# SCH2024-02-13.net
KiCad netlist of a schematic drawn in EasyEDA
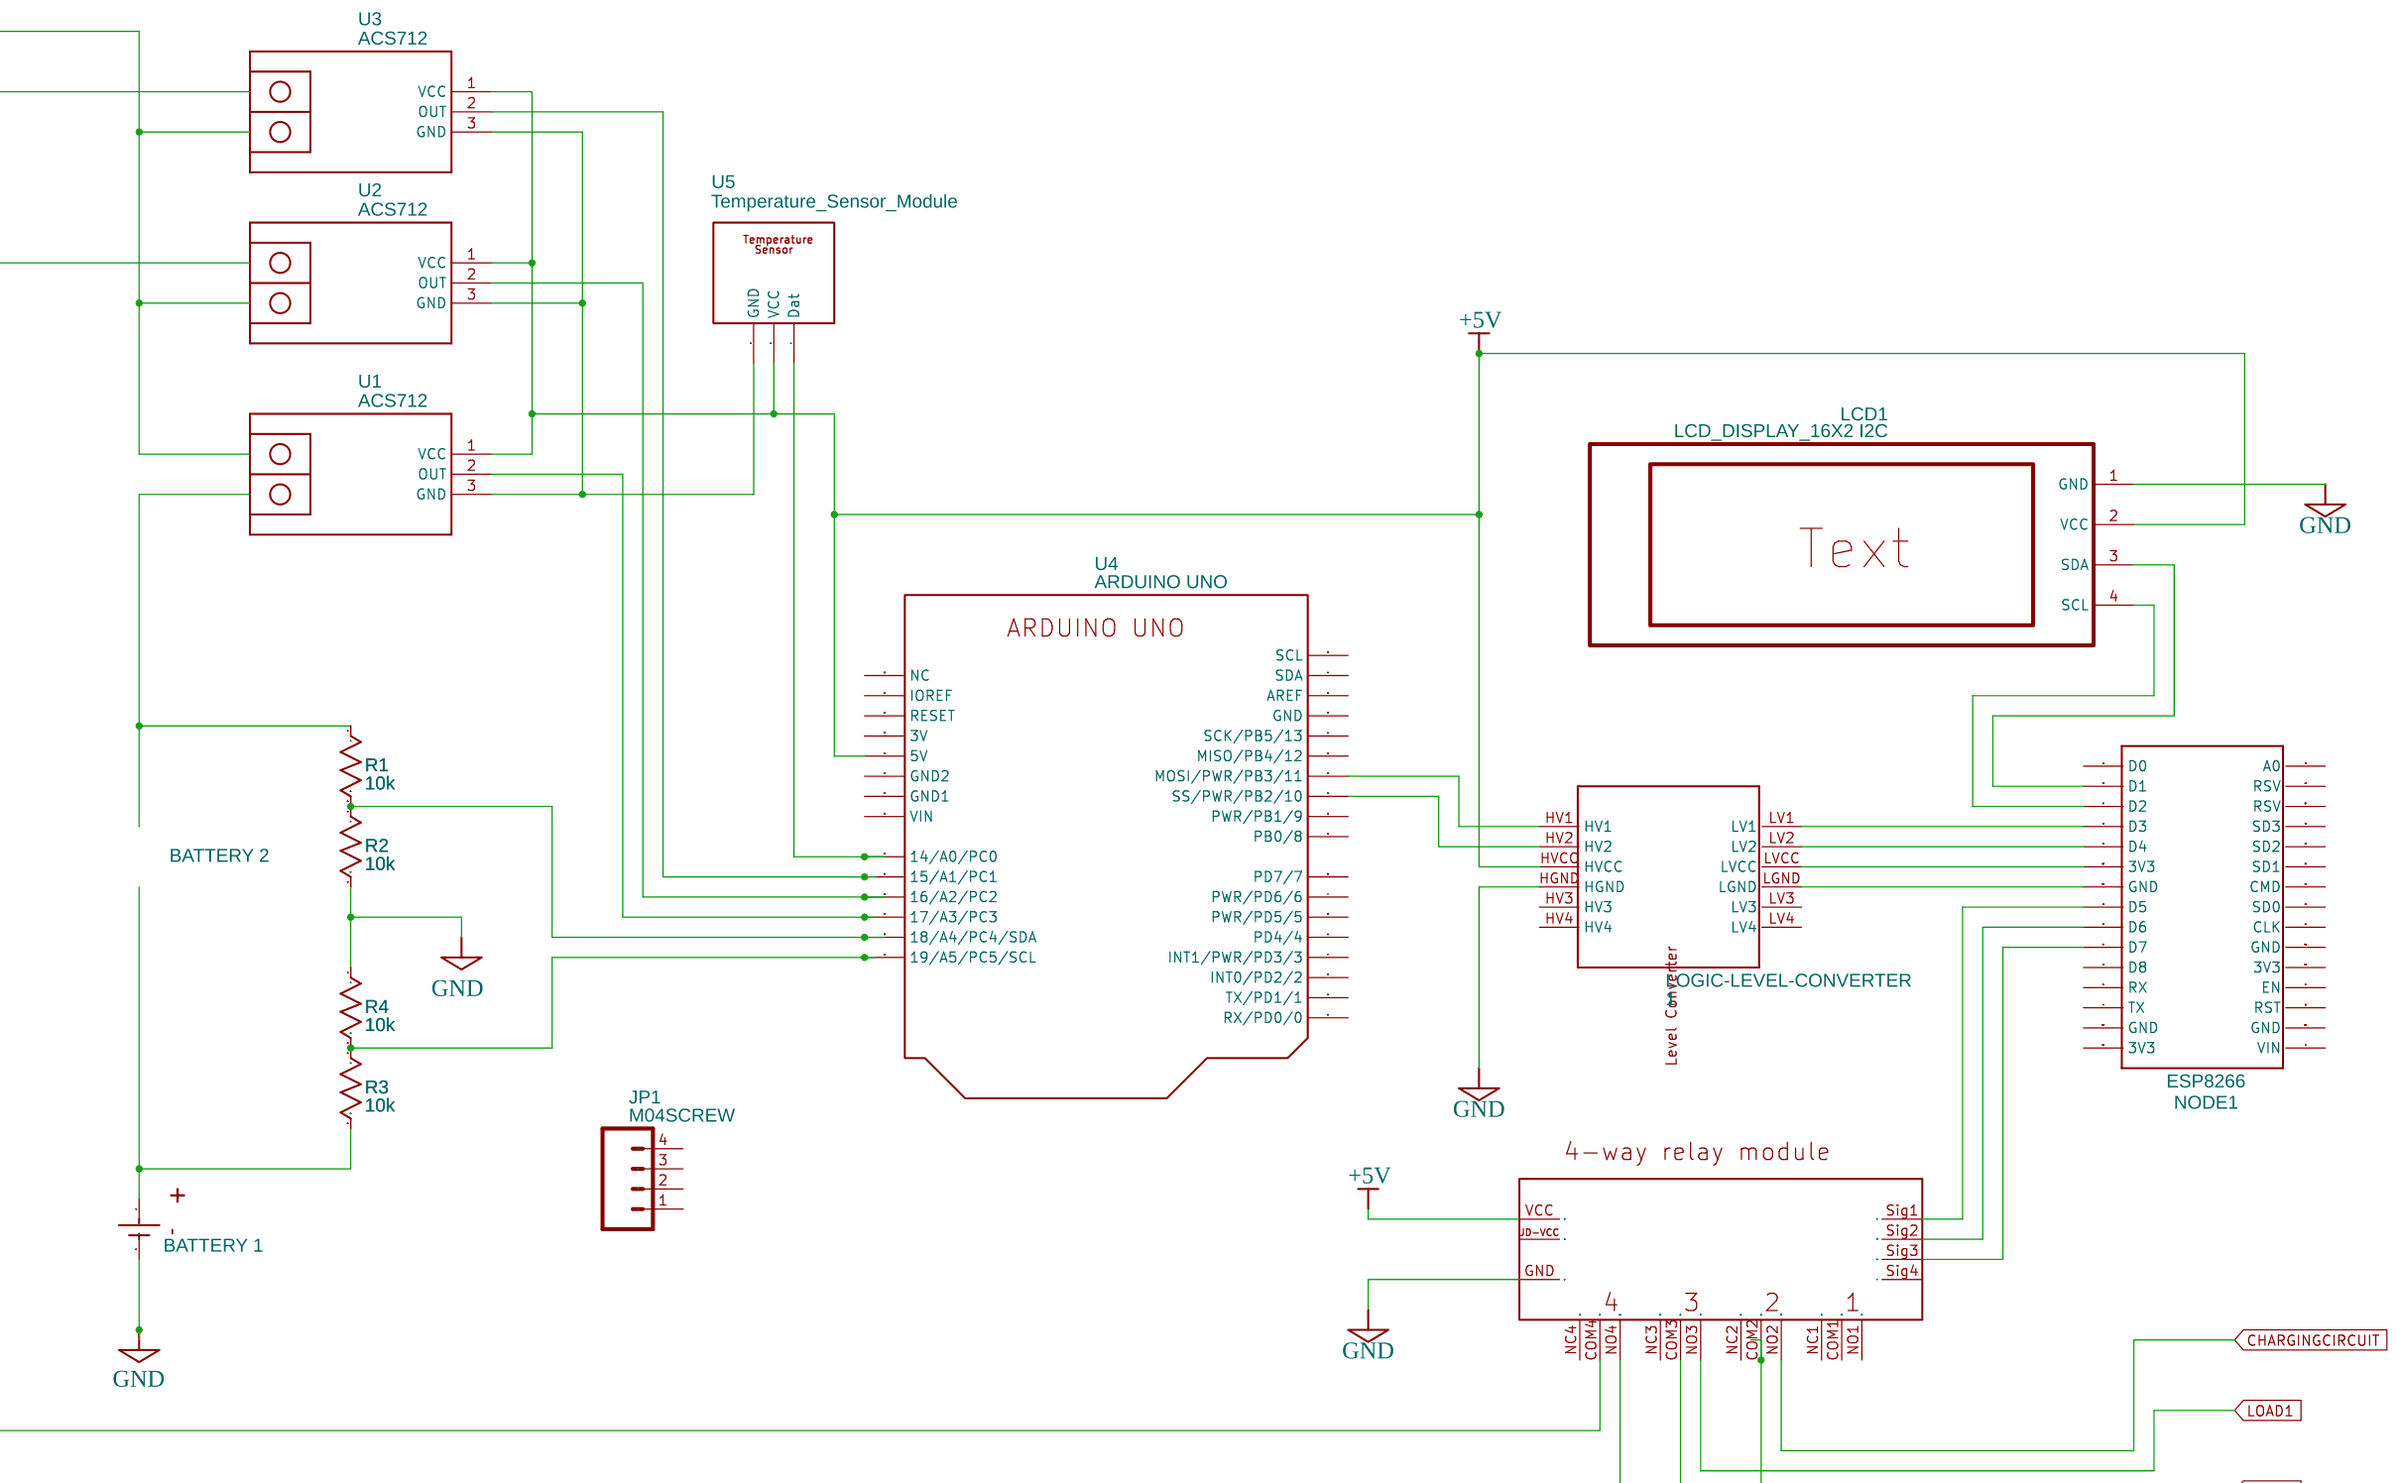
[diagram p0: schematic sheet]

(export (version "E")
  (design (tool "Eeschema 10.0.6"))
  (components
    (comp (ref "1") (value "LOGIC-LEVEL-CONVERTER") (libsource (lib "") (part "LOGIC-LEVEL-CONVERTER")))
    (comp (ref "G2") (value "BATTERY 1") (libsource (lib "") (part "BATTERY-1ELEMENT_RevE_Date15jun2010")))
    (comp (ref "JP1") (value "M04SCREW") (libsource (lib "") (part "M04SCREW")))
    (comp (ref "LCD1") (value "LCD_DISPLAY_16X2 I2C") (libsource (lib "") (part "LCD_DISPLAY_16X2 I2C")))
    (comp (ref "NODE1") (value "ESP8266") (libsource (lib "") (part "ESP8266 COPY")))
    (comp (ref "R1") (value "10k") (libsource (lib "") (part "R_0603_US")))
    (comp (ref "R2") (value "10k") (libsource (lib "") (part "R_0603_US")))
    (comp (ref "R3") (value "10k") (libsource (lib "") (part "R_0603_US")))
    (comp (ref "R4") (value "10k") (libsource (lib "") (part "R_0603_US")))
    (comp (ref "U1") (value "ACS712") (libsource (lib "") (part "CURRENT-SENSOR-ACS712")))
    (comp (ref "U2") (value "ACS712") (libsource (lib "") (part "CURRENT-SENSOR-ACS712")))
    (comp (ref "U3") (value "ACS712") (libsource (lib "") (part "CURRENT-SENSOR-ACS712")))
    (comp (ref "U4") (value "ARDUINO UNO") (libsource (lib "") (part "ARDUINO UNO")))
    (comp (ref "U5")
      (value "Temperature_Sensor_Module")
      (libsource (lib "") (part "DS18B20_Temperature_Sensor_Module"))
    )
    (comp (ref "U6") (value "4 way relay") (libsource (lib "") (part "4 way relay")))
  )
  (nets
    (net (code "1") (name "+5V") (class "Default")
      (node (ref "1") (pin "HVCC") (pinfunction "HVCC_HVCC") (pintype "bidirectional"))
      (node (ref "LCD1") (pin "2") (pinfunction "VCC_2") (pintype "passive"))
      (node (ref "U1") (pin "1") (pinfunction "VCC_1") (pintype "passive"))
      (node (ref "U2") (pin "1") (pinfunction "VCC_1") (pintype "passive"))
      (node (ref "U3") (pin "1") (pinfunction "VCC_1") (pintype "passive"))
      (node (ref "U4") (pin "28") (pinfunction "5V_28") (pintype "passive"))
      (node (ref "U5") (pin "2") (pinfunction "VCC_2") (pintype "unspecified"))
      (node (ref "U6") (pin "VCC") (pinfunction "6_VCC") (pintype "unspecified"))
    )
    (net (code "2") (name "CHARGINGCIRCUIT") (class "Default")
      (node (ref "U6") (pin "NO2") (pinfunction "8_NO2") (pintype "unspecified"))
    )
    (net (code "3") (name "GND") (class "Default")
      (node (ref "1") (pin "HGND") (pinfunction "HGND_HGND") (pintype "bidirectional"))
      (node (ref "G2") (pin "2") (pinfunction "Minus_2") (pintype "bidirectional"))
      (node (ref "LCD1") (pin "1") (pinfunction "GND_1") (pintype "passive"))
      (node (ref "R2") (pin "2") (pinfunction "2_2") (pintype "unspecified"))
      (node (ref "R4") (pin "1") (pinfunction "1_1") (pintype "unspecified"))
      (node (ref "U6") (pin "GND") (pinfunction "5_GND") (pintype "unspecified"))
    )
    (net (code "4") (name "LOAD1") (class "Default")
      (node (ref "U6") (pin "NO3") (pinfunction "8_NO3") (pintype "unspecified"))
    )
    (net (code "5") (name "LOAD2") (class "Default")
      (node (ref "U6") (pin "NO4") (pinfunction "8_NO4") (pintype "unspecified"))
    )
    (net (code "6") (name "Net-(1-PadLGND)") (class "Default")
      (node (ref "1") (pin "LGND") (pinfunction "LGND_LGND") (pintype "bidirectional"))
      (node (ref "NODE1") (pin "GND@2") (pinfunction "GND_GND@2") (pintype "bidirectional"))
    )
    (net (code "7") (name "Net-(1-PadLV1)") (class "Default")
      (node (ref "1") (pin "LV1") (pinfunction "LV1_LV1") (pintype "bidirectional"))
      (node (ref "NODE1") (pin "D3") (pinfunction "D3_D3") (pintype "bidirectional"))
    )
    (net (code "8") (name "Net-(1-PadLV2)") (class "Default")
      (node (ref "1") (pin "LV2") (pinfunction "LV2_LV2") (pintype "bidirectional"))
      (node (ref "NODE1") (pin "D4") (pinfunction "D4_D4") (pintype "bidirectional"))
    )
    (net (code "9") (name "Net-(1-PadLVCC)") (class "Default")
      (node (ref "1") (pin "LVCC") (pinfunction "LVCC_LVCC") (pintype "bidirectional"))
      (node (ref "NODE1") (pin "3V3@2") (pinfunction "3V3_3V3@2") (pintype "bidirectional"))
    )
    (net (code "10") (name "Net-(G2-Plus)") (class "Default")
      (node (ref "G2") (pin "1") (pinfunction "Plus_1") (pintype "bidirectional"))
      (node (ref "R3") (pin "2") (pinfunction "2_2") (pintype "unspecified"))
    )
    (net (code "11") (name "Net-(LCD1-SCL)") (class "Default")
      (node (ref "LCD1") (pin "4") (pinfunction "SCL_4") (pintype "passive"))
      (node (ref "NODE1") (pin "D2") (pinfunction "D2_D2") (pintype "bidirectional"))
    )
    (net (code "12") (name "Net-(LCD1-SDA)") (class "Default")
      (node (ref "LCD1") (pin "3") (pinfunction "SDA_3") (pintype "passive"))
      (node (ref "NODE1") (pin "D1") (pinfunction "D1_D1") (pintype "bidirectional"))
    )
    (net (code "13") (name "Net-(U1-GND)") (class "Default")
      (node (ref "U1") (pin "3") (pinfunction "GND_3") (pintype "passive"))
      (node (ref "U2") (pin "3") (pinfunction "GND_3") (pintype "passive"))
      (node (ref "U3") (pin "3") (pinfunction "GND_3") (pintype "passive"))
      (node (ref "U5") (pin "3") (pinfunction "GND_3") (pintype "unspecified"))
    )
    (net (code "14") (name "Net-(U1-OUT)") (class "Default")
      (node (ref "U1") (pin "2") (pinfunction "OUT_2") (pintype "output"))
      (node (ref "U4") (pin "21") (pinfunction "17/A3/PC3_21") (pintype "unspecified"))
    )
    (net (code "15") (name "Net-(U2-OUT)") (class "Default")
      (node (ref "U2") (pin "2") (pinfunction "OUT_2") (pintype "output"))
      (node (ref "U4") (pin "22") (pinfunction "16/A2/PC2_22") (pintype "unspecified"))
    )
    (net (code "16") (name "Net-(U3-OUT)") (class "Default")
      (node (ref "U3") (pin "2") (pinfunction "OUT_2") (pintype "output"))
      (node (ref "U4") (pin "23") (pinfunction "15/A1/PC1_23") (pintype "unspecified"))
    )
    (net (code "17") (name "Net-(U4-14{slash}A0{slash}PC0)") (class "Default")
      (node (ref "U4") (pin "24") (pinfunction "14/A0/PC0_24") (pintype "unspecified"))
      (node (ref "U5") (pin "1") (pinfunction "Dat_1") (pintype "unspecified"))
    )
    (net (code "18") (name "Net-(U4-18{slash}A4{slash}PC4{slash}SDA)") (class "Default")
      (node (ref "R1") (pin "2") (pinfunction "2_2") (pintype "unspecified"))
      (node (ref "R2") (pin "1") (pinfunction "1_1") (pintype "unspecified"))
      (node (ref "U4") (pin "20") (pinfunction "18/A4/PC4/SDA_20") (pintype "unspecified"))
    )
    (net (code "19") (name "Net-(U4-19{slash}A5{slash}PC5{slash}SCL)") (class "Default")
      (node (ref "R3") (pin "1") (pinfunction "1_1") (pintype "unspecified"))
      (node (ref "R4") (pin "2") (pinfunction "2_2") (pintype "unspecified"))
      (node (ref "U4") (pin "19") (pinfunction "19/A5/PC5/SCL_19") (pintype "unspecified"))
    )
    (net (code "20") (name "Net-(U4-MOSI{slash}PWR{slash}PB3{slash}11)") (class "Default")
      (node (ref "1") (pin "HV1") (pinfunction "HV1_HV1") (pintype "bidirectional"))
      (node (ref "U4") (pin "12") (pinfunction "MOSI/PWR/PB3/11_12") (pintype "unspecified"))
    )
    (net (code "21") (name "Net-(U4-SS{slash}PWR{slash}PB2{slash}10)") (class "Default")
      (node (ref "1") (pin "HV2") (pinfunction "HV2_HV2") (pintype "bidirectional"))
      (node (ref "U4") (pin "11") (pinfunction "SS/PWR/PB2/10_11") (pintype "unspecified"))
    )
    (net (code "22") (name "Net-(U6-1)") (class "Default")
      (node (ref "NODE1") (pin "D5") (pinfunction "D5_D5") (pintype "bidirectional"))
      (node (ref "U6") (pin "Sig1") (pinfunction "1_Sig1") (pintype "unspecified"))
    )
    (net (code "23") (name "Net-(U6-2)") (class "Default")
      (node (ref "NODE1") (pin "D6") (pinfunction "D6_D6") (pintype "bidirectional"))
      (node (ref "U6") (pin "Sig2") (pinfunction "2_Sig2") (pintype "unspecified"))
    )
    (net (code "24") (name "Net-(U6-3)") (class "Default")
      (node (ref "NODE1") (pin "D7") (pinfunction "D7_D7") (pintype "bidirectional"))
      (node (ref "U6") (pin "Sig3") (pinfunction "3_Sig3") (pintype "unspecified"))
    )
    (net (code "25") (name "unconnected-(1-PadHV3)") (class "Default")
      (node (ref "1") (pin "HV3") (pinfunction "HV3_HV3") (pintype "bidirectional"))
    )
    (net (code "26") (name "unconnected-(1-PadHV4)") (class "Default")
      (node (ref "1") (pin "HV4") (pinfunction "HV4_HV4") (pintype "bidirectional"))
    )
    (net (code "27") (name "unconnected-(1-PadLV3)") (class "Default")
      (node (ref "1") (pin "LV3") (pinfunction "LV3_LV3") (pintype "bidirectional"))
    )
    (net (code "28") (name "unconnected-(1-PadLV4)") (class "Default")
      (node (ref "1") (pin "LV4") (pinfunction "LV4_LV4") (pintype "bidirectional"))
    )
    (net (code "29") (name "unconnected-(JP1-Pad1)") (class "Default")
      (node (ref "JP1") (pin "1") (pinfunction "1_1") (pintype "unspecified"))
    )
    (net (code "30") (name "unconnected-(JP1-Pad2)") (class "Default")
      (node (ref "JP1") (pin "2") (pinfunction "2_2") (pintype "unspecified"))
    )
    (net (code "31") (name "unconnected-(JP1-Pad3)") (class "Default")
      (node (ref "JP1") (pin "3") (pinfunction "3_3") (pintype "unspecified"))
    )
    (net (code "32") (name "unconnected-(JP1-Pad4)") (class "Default")
      (node (ref "JP1") (pin "4") (pinfunction "4_4") (pintype "unspecified"))
    )
    (net (code "33") (name "unconnected-(NODE1-3V3-Pad3V3@1)") (class "Default")
      (node (ref "NODE1") (pin "3V3@1") (pinfunction "3V3_3V3@1") (pintype "bidirectional"))
    )
    (net (code "34") (name "unconnected-(NODE1-3V3-Pad3V3@3)") (class "Default")
      (node (ref "NODE1") (pin "3V3@3") (pinfunction "3V3_3V3@3") (pintype "bidirectional"))
    )
    (net (code "35") (name "unconnected-(NODE1-GND-PadGND@1)") (class "Default")
      (node (ref "NODE1") (pin "GND@1") (pinfunction "GND_GND@1") (pintype "bidirectional"))
    )
    (net (code "36") (name "unconnected-(NODE1-GND-PadGND@3)") (class "Default")
      (node (ref "NODE1") (pin "GND@3") (pinfunction "GND_GND@3") (pintype "bidirectional"))
    )
    (net (code "37") (name "unconnected-(NODE1-GND-PadGND@4)") (class "Default")
      (node (ref "NODE1") (pin "GND@4") (pinfunction "GND_GND@4") (pintype "bidirectional"))
    )
    (net (code "38") (name "unconnected-(NODE1-PadA0)") (class "Default")
      (node (ref "NODE1") (pin "A0") (pinfunction "A0_A0") (pintype "bidirectional"))
    )
    (net (code "39") (name "unconnected-(NODE1-PadCLK)") (class "Default")
      (node (ref "NODE1") (pin "CLK") (pinfunction "CLK_CLK") (pintype "bidirectional"))
    )
    (net (code "40") (name "unconnected-(NODE1-PadCMD)") (class "Default")
      (node (ref "NODE1") (pin "CMD") (pinfunction "CMD_CMD") (pintype "bidirectional"))
    )
    (net (code "41") (name "unconnected-(NODE1-PadD0)") (class "Default")
      (node (ref "NODE1") (pin "D0") (pinfunction "D0_D0") (pintype "bidirectional"))
    )
    (net (code "42") (name "unconnected-(NODE1-PadD8)") (class "Default")
      (node (ref "NODE1") (pin "D8") (pinfunction "D8_D8") (pintype "bidirectional"))
    )
    (net (code "43") (name "unconnected-(NODE1-PadEN)") (class "Default")
      (node (ref "NODE1") (pin "EN") (pinfunction "EN_EN") (pintype "bidirectional"))
    )
    (net (code "44") (name "unconnected-(NODE1-PadRST)") (class "Default")
      (node (ref "NODE1") (pin "RST") (pinfunction "RST_RST") (pintype "bidirectional"))
    )
    (net (code "45") (name "unconnected-(NODE1-PadRX)") (class "Default")
      (node (ref "NODE1") (pin "RX") (pinfunction "RX_RX") (pintype "bidirectional"))
    )
    (net (code "46") (name "unconnected-(NODE1-PadSD1)") (class "Default")
      (node (ref "NODE1") (pin "SD1") (pinfunction "SD1_SD1") (pintype "bidirectional"))
    )
    (net (code "47") (name "unconnected-(NODE1-PadSD2)") (class "Default")
      (node (ref "NODE1") (pin "SD2") (pinfunction "SD2_SD2") (pintype "bidirectional"))
    )
    (net (code "48") (name "unconnected-(NODE1-PadSD3)") (class "Default")
      (node (ref "NODE1") (pin "SD3") (pinfunction "SD3_SD3") (pintype "bidirectional"))
    )
    (net (code "49") (name "unconnected-(NODE1-PadTX)") (class "Default")
      (node (ref "NODE1") (pin "TX") (pinfunction "TX_TX") (pintype "bidirectional"))
    )
    (net (code "50") (name "unconnected-(NODE1-PadVIN)") (class "Default")
      (node (ref "NODE1") (pin "VIN") (pinfunction "VIN_VIN") (pintype "bidirectional"))
    )
    (net (code "51") (name "unconnected-(NODE1-RSV-PadRSV1)") (class "Default")
      (node (ref "NODE1") (pin "RSV1") (pinfunction "RSV_RSV1") (pintype "bidirectional"))
    )
    (net (code "52") (name "unconnected-(NODE1-RSV-PadRSV2)") (class "Default")
      (node (ref "NODE1") (pin "RSV2") (pinfunction "RSV_RSV2") (pintype "bidirectional"))
    )
    (net (code "53") (name "unconnected-(NODE1-SD0-PadSDO)") (class "Default")
      (node (ref "NODE1") (pin "SDO") (pinfunction "SD0_SDO") (pintype "bidirectional"))
    )
    (net (code "54") (name "unconnected-(R1-Pad1)") (class "Default")
      (node (ref "R1") (pin "1") (pinfunction "1_1") (pintype "unspecified"))
    )
    (net (code "55") (name "unconnected-(U4-3V-Pad29)") (class "Default")
      (node (ref "U4") (pin "29") (pinfunction "3V_29") (pintype "passive"))
    )
    (net (code "56") (name "unconnected-(U4-AREF-Pad16)") (class "Default")
      (node (ref "U4") (pin "16") (pinfunction "AREF_16") (pintype "unspecified"))
    )
    (net (code "57") (name "unconnected-(U4-GND-Pad15)") (class "Default")
      (node (ref "U4") (pin "15") (pinfunction "GND_15") (pintype "passive"))
    )
    (net (code "58") (name "unconnected-(U4-GND1-Pad26)") (class "Default")
      (node (ref "U4") (pin "26") (pinfunction "GND1_26") (pintype "passive"))
    )
    (net (code "59") (name "unconnected-(U4-GND2-Pad27)") (class "Default")
      (node (ref "U4") (pin "27") (pinfunction "GND2_27") (pintype "passive"))
    )
    (net (code "60") (name "unconnected-(U4-INT0{slash}PD2{slash}2-Pad3)") (class "Default")
      (node (ref "U4") (pin "3") (pinfunction "INT0/PD2/2_3") (pintype "unspecified"))
    )
    (net (code "61") (name "unconnected-(U4-INT1{slash}PWR{slash}PD3{slash}3-Pad4)") (class "Default")
      (node (ref "U4") (pin "4") (pinfunction "INT1/PWR/PD3/3_4") (pintype "unspecified"))
    )
    (net (code "62") (name "unconnected-(U4-IOREF-Pad31)") (class "Default")
      (node (ref "U4") (pin "31") (pinfunction "IOREF_31") (pintype "unspecified"))
    )
    (net (code "63") (name "unconnected-(U4-MISO{slash}PB4{slash}12-Pad13)") (class "Default")
      (node (ref "U4") (pin "13") (pinfunction "MISO/PB4/12_13") (pintype "unspecified"))
    )
    (net (code "64") (name "unconnected-(U4-NC-Pad32)") (class "Default")
      (node (ref "U4") (pin "32") (pinfunction "NC_32") (pintype "unspecified"))
    )
    (net (code "65") (name "unconnected-(U4-PB0{slash}8-Pad9)") (class "Default")
      (node (ref "U4") (pin "9") (pinfunction "PB0/8_9") (pintype "unspecified"))
    )
    (net (code "66") (name "unconnected-(U4-PD4{slash}4-Pad5)") (class "Default")
      (node (ref "U4") (pin "5") (pinfunction "PD4/4_5") (pintype "unspecified"))
    )
    (net (code "67") (name "unconnected-(U4-PD7{slash}7-Pad8)") (class "Default")
      (node (ref "U4") (pin "8") (pinfunction "PD7/7_8") (pintype "unspecified"))
    )
    (net (code "68") (name "unconnected-(U4-PWR{slash}PB1{slash}9-Pad10)") (class "Default")
      (node (ref "U4") (pin "10") (pinfunction "PWR/PB1/9_10") (pintype "unspecified"))
    )
    (net (code "69") (name "unconnected-(U4-PWR{slash}PD5{slash}5-Pad6)") (class "Default")
      (node (ref "U4") (pin "6") (pinfunction "PWR/PD5/5_6") (pintype "unspecified"))
    )
    (net (code "70") (name "unconnected-(U4-PWR{slash}PD6{slash}6-Pad7)") (class "Default")
      (node (ref "U4") (pin "7") (pinfunction "PWR/PD6/6_7") (pintype "unspecified"))
    )
    (net (code "71") (name "unconnected-(U4-RESET-Pad30)") (class "Default")
      (node (ref "U4") (pin "30") (pinfunction "RESET_30") (pintype "unspecified"))
    )
    (net (code "72") (name "unconnected-(U4-RX{slash}PD0{slash}0-Pad1)") (class "Default")
      (node (ref "U4") (pin "1") (pinfunction "RX/PD0/0_1") (pintype "unspecified"))
    )
    (net (code "73") (name "unconnected-(U4-SCK{slash}PB5{slash}13-Pad14)") (class "Default")
      (node (ref "U4") (pin "14") (pinfunction "SCK/PB5/13_14") (pintype "unspecified"))
    )
    (net (code "74") (name "unconnected-(U4-SCL-Pad18)") (class "Default")
      (node (ref "U4") (pin "18") (pinfunction "SCL_18") (pintype "unspecified"))
    )
    (net (code "75") (name "unconnected-(U4-SDA-Pad17)") (class "Default")
      (node (ref "U4") (pin "17") (pinfunction "SDA_17") (pintype "unspecified"))
    )
    (net (code "76") (name "unconnected-(U4-TX{slash}PD1{slash}1-Pad2)") (class "Default")
      (node (ref "U4") (pin "2") (pinfunction "TX/PD1/1_2") (pintype "unspecified"))
    )
    (net (code "77") (name "unconnected-(U4-VIN-Pad25)") (class "Default")
      (node (ref "U4") (pin "25") (pinfunction "VIN_25") (pintype "passive"))
    )
    (net (code "78") (name "unconnected-(U6-4-PadSig4)") (class "Default")
      (node (ref "U6") (pin "Sig4") (pinfunction "4_Sig4") (pintype "unspecified"))
    )
    (net (code "79") (name "unconnected-(U6-6-PadJD-VCC)") (class "Default")
      (node (ref "U6") (pin "JD-VCC") (pinfunction "6_JD-VCC") (pintype "unspecified"))
    )
    (net (code "80") (name "unconnected-(U6-8-PadCOM1)") (class "Default")
      (node (ref "U6") (pin "COM1") (pinfunction "8_COM1") (pintype "unspecified"))
    )
    (net (code "81") (name "unconnected-(U6-8-PadCOM2)") (class "Default")
      (node (ref "U6") (pin "COM2") (pinfunction "8_COM2") (pintype "unspecified"))
    )
    (net (code "82") (name "unconnected-(U6-8-PadCOM3)") (class "Default")
      (node (ref "U6") (pin "COM3") (pinfunction "8_COM3") (pintype "unspecified"))
    )
    (net (code "83") (name "unconnected-(U6-8-PadCOM4)") (class "Default")
      (node (ref "U6") (pin "COM4") (pinfunction "8_COM4") (pintype "unspecified"))
    )
    (net (code "84") (name "unconnected-(U6-8-PadNC1)") (class "Default")
      (node (ref "U6") (pin "NC1") (pinfunction "8_NC1") (pintype "unspecified"))
    )
    (net (code "85") (name "unconnected-(U6-8-PadNC2)") (class "Default")
      (node (ref "U6") (pin "NC2") (pinfunction "8_NC2") (pintype "unspecified"))
    )
    (net (code "86") (name "unconnected-(U6-8-PadNC3)") (class "Default")
      (node (ref "U6") (pin "NC3") (pinfunction "8_NC3") (pintype "unspecified"))
    )
    (net (code "87") (name "unconnected-(U6-8-PadNC4)") (class "Default")
      (node (ref "U6") (pin "NC4") (pinfunction "8_NC4") (pintype "unspecified"))
    )
    (net (code "88") (name "unconnected-(U6-8-PadNO1)") (class "Default")
      (node (ref "U6") (pin "NO1") (pinfunction "8_NO1") (pintype "unspecified"))
    )
  )
)
